# design.net
KiCad netlist of a schematic drawn in Altium Designer
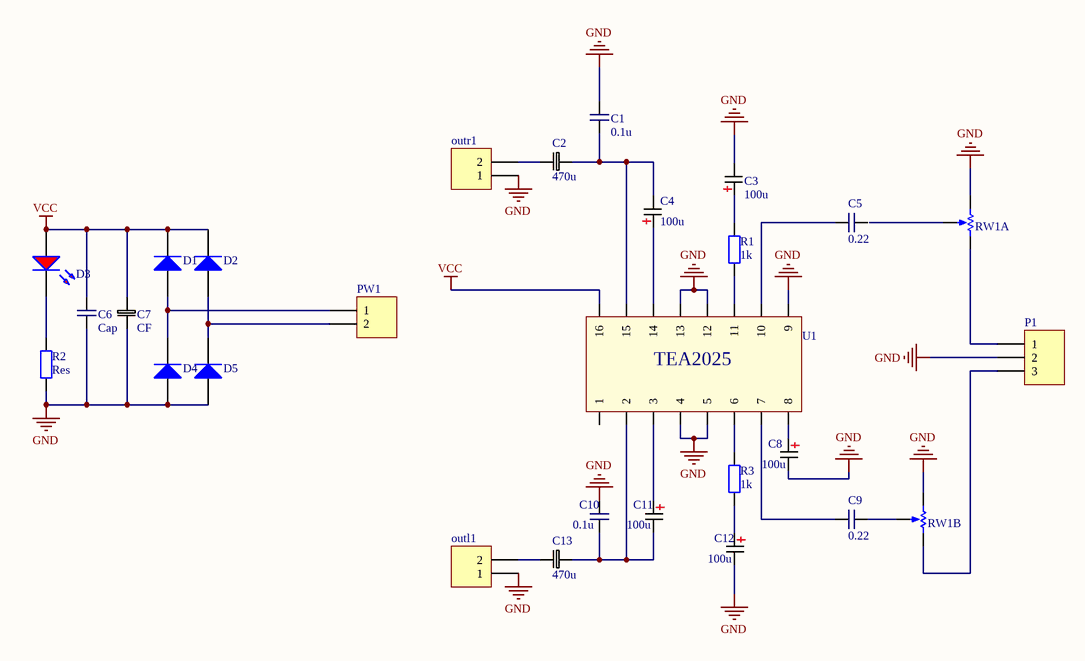
[diagram p0: 原理图.SchDoc]

(export (version "E")
  (design (tool "Eeschema 10.0.6"))
  (components
    (comp (ref "C1") (value "0.1u") (footprint "RAD0.1") (libsource (lib "Schlib1") (part "Cap")))
    (comp (ref "C2") (value "470u") (footprint "CF0.1-6.5") (libsource (lib "Schlib1") (part "CF")))
    (comp (ref "C3") (value "100u") (footprint "CF0.1") (libsource (lib "Schlib1") (part "Cap Pol")))
    (comp (ref "C4") (value "100u") (footprint "CF0.1") (libsource (lib "Schlib1") (part "Cap Pol")))
    (comp (ref "C5") (value "0.22") (footprint "RAD0.1") (libsource (lib "Schlib1") (part "Cap")))
    (comp (ref "C6") (value "Cap") (footprint "RAD0.1") (libsource (lib "MY") (part "Cap")))
    (comp (ref "C7") (value "CF") (footprint "CF0.2-13") (libsource (lib "MY") (part "CF")))
    (comp (ref "C8") (value "100u") (footprint "CF0.2-13") (libsource (lib "Schlib1") (part "Cap Pol")))
    (comp (ref "C9") (value "0.22") (footprint "RAD0.1") (libsource (lib "Schlib1") (part "Cap")))
    (comp (ref "C10") (value "0.1u") (footprint "RAD0.1") (libsource (lib "Schlib1") (part "Cap")))
    (comp (ref "C11") (value "100u") (footprint "CF0.1") (libsource (lib "Schlib1") (part "Cap Pol")))
    (comp (ref "C12") (value "100u") (footprint "CF0.1") (libsource (lib "Schlib1") (part "Cap Pol")))
    (comp (ref "C13") (value "470u") (footprint "CF0.1-6.5") (libsource (lib "Schlib1") (part "CF")))
    (comp (ref "D1")
      (value "Diode 1N4007")
      (footprint "DIO10.46-5.3x2.8")
      (description "1 Amp General Purpose Rectifier")
      (fields (field (name "PUBLISHER") "Altium Limited"))
      (libsource (lib "Miscellaneous Devices") (part "Diode 1N4007"))
    )
    (comp (ref "D2")
      (value "Diode 1N4007")
      (footprint "DIO10.46-5.3x2.8")
      (description "1 Amp General Purpose Rectifier")
      (fields (field (name "PUBLISHER") "Altium Limited"))
      (libsource (lib "Miscellaneous Devices") (part "Diode 1N4007"))
    )
    (comp (ref "D3")
      (value "LED0")
      (footprint "LED")
      (fields (field (name "PUBLISHER") "Altium Limited"))
      (libsource (lib "MY") (part "LED0"))
    )
    (comp (ref "D4")
      (value "Diode 1N4007")
      (footprint "DIO10.46-5.3x2.8")
      (description "1 Amp General Purpose Rectifier")
      (fields (field (name "PUBLISHER") "Altium Limited"))
      (libsource (lib "Miscellaneous Devices") (part "Diode 1N4007"))
    )
    (comp (ref "D5")
      (value "Diode 1N4007")
      (footprint "DIO10.46-5.3x2.8")
      (description "1 Amp General Purpose Rectifier")
      (fields (field (name "PUBLISHER") "Altium Limited"))
      (libsource (lib "Miscellaneous Devices") (part "Diode 1N4007"))
    )
    (comp (ref "outl1")
      (value "Header 2")
      (footprint "HDR1X2")
      (description "Header, 2-Pin")
      (fields (field (name "PUBLISHER") "Altium Limited"))
      (libsource (lib "") (part "Header 2_1"))
    )
    (comp (ref "outr1")
      (value "Header 2")
      (footprint "HDR1X2")
      (description "Header, 2-Pin")
      (fields (field (name "PUBLISHER") "Altium Limited"))
      (libsource (lib "") (part "Header 2_1"))
    )
    (comp (ref "P1")
      (value "Header 3")
      (footprint "HDR1X3")
      (description "Header, 3-Pin")
      (fields (field (name "PUBLISHER") "Altium Limited"))
      (libsource (lib "Miscellaneous Connectors") (part "Header 3"))
    )
    (comp (ref "PW1")
      (value "Header 2")
      (footprint "HDR1X2")
      (description "Header, 2-Pin")
      (fields (field (name "PUBLISHER") "Altium Limited"))
      (libsource (lib "Miscellaneous Connectors") (part "Header 2"))
    )
    (comp (ref "R1")
      (value "1k")
      (footprint "RAD0.1")
      (description "Resistor")
      (fields (field (name "PUBLISHER") "Altium Limited"))
      (libsource (lib "") (part "Res_1"))
    )
    (comp (ref "R2")
      (value "Res")
      (footprint "AXIAL-0.3")
      (description "Resistor")
      (fields (field (name "PUBLISHER") "Altium Limited"))
      (libsource (lib "MY") (part "Res"))
    )
    (comp (ref "R3")
      (value "1k")
      (footprint "RAD0.1")
      (description "Resistor")
      (fields (field (name "PUBLISHER") "Altium Limited"))
      (libsource (lib "Schlib1") (part "Res"))
    )
    (comp (ref "RW1") (value "RW") (footprint "RW") (libsource (lib "Schlib1") (part "RW")))
    (comp (ref "U1") (value "TEA2025") (footprint "DIP16") (libsource (lib "Schlib1") (part "TEA2025")))
  )
  (nets
    (net (code "1") (name "GND") (class "Default")
      (node (ref "C1") (pin "1") (pinfunction "1_1") (pintype "passive"))
      (node (ref "C10") (pin "1") (pinfunction "1_1") (pintype "passive"))
      (node (ref "C12") (pin "2") (pinfunction "2_2") (pintype "passive"))
      (node (ref "C3") (pin "2") (pinfunction "2_2") (pintype "passive"))
      (node (ref "C6") (pin "1") (pinfunction "1_1") (pintype "passive"))
      (node (ref "C7") (pin "2") (pinfunction "2_2") (pintype "passive"))
      (node (ref "C8") (pin "2") (pinfunction "2_2") (pintype "passive"))
      (node (ref "D4") (pin "1") (pinfunction "A_1") (pintype "passive"))
      (node (ref "D5") (pin "1") (pinfunction "A_1") (pintype "passive"))
      (node (ref "P1") (pin "2") (pinfunction "2_2") (pintype "passive"))
      (node (ref "R2") (pin "1") (pinfunction "1_1") (pintype "passive"))
      (node (ref "RW1") (pin "1") (pinfunction "TOP_1") (pintype "passive"))
      (node (ref "RW1") (pin "4") (pinfunction "TOP_4") (pintype "passive"))
      (node (ref "U1") (pin "12") (pinfunction "12_12") (pintype "passive"))
      (node (ref "U1") (pin "13") (pinfunction "13_13") (pintype "passive"))
      (node (ref "U1") (pin "4") (pinfunction "4_4") (pintype "passive"))
      (node (ref "U1") (pin "5") (pinfunction "5_5") (pintype "passive"))
      (node (ref "U1") (pin "9") (pinfunction "9_9") (pintype "passive"))
      (node (ref "outl1") (pin "1") (pinfunction "1_1") (pintype "passive"))
      (node (ref "outr1") (pin "1") (pinfunction "1_1") (pintype "passive"))
    )
    (net (code "2") (name "Net-(C1-Pad2)") (class "Default")
      (node (ref "C1") (pin "2") (pinfunction "2_2") (pintype "passive"))
      (node (ref "C2") (pin "1") (pinfunction "1_1") (pintype "passive"))
      (node (ref "C4") (pin "2") (pinfunction "2_2") (pintype "passive"))
      (node (ref "U1") (pin "15") (pinfunction "15_15") (pintype "passive"))
    )
    (net (code "3") (name "Net-(C2-Pad2)") (class "Default")
      (node (ref "C2") (pin "2") (pinfunction "2_2") (pintype "passive"))
      (node (ref "outr1") (pin "2") (pinfunction "2_2") (pintype "passive"))
    )
    (net (code "4") (name "Net-(C3-Pad1)") (class "Default")
      (node (ref "C3") (pin "1") (pinfunction "1_1") (pintype "passive"))
      (node (ref "R1") (pin "1") (pinfunction "1_1") (pintype "passive"))
    )
    (net (code "5") (name "Net-(C4-Pad1)") (class "Default")
      (node (ref "C4") (pin "1") (pinfunction "1_1") (pintype "passive"))
      (node (ref "U1") (pin "14") (pinfunction "14_14") (pintype "passive"))
    )
    (net (code "6") (name "Net-(C5-Pad1)") (class "Default")
      (node (ref "C5") (pin "1") (pinfunction "1_1") (pintype "passive"))
      (node (ref "U1") (pin "10") (pinfunction "10_10") (pintype "passive"))
    )
    (net (code "7") (name "Net-(C8-Pad1)") (class "Default")
      (node (ref "C8") (pin "1") (pinfunction "1_1") (pintype "passive"))
      (node (ref "U1") (pin "8") (pinfunction "8_8") (pintype "passive"))
    )
    (net (code "8") (name "Net-(C9-Pad1)") (class "Default")
      (node (ref "C9") (pin "1") (pinfunction "1_1") (pintype "passive"))
      (node (ref "U1") (pin "7") (pinfunction "7_7") (pintype "passive"))
    )
    (net (code "9") (name "Net-(C10-Pad2)") (class "Default")
      (node (ref "C10") (pin "2") (pinfunction "2_2") (pintype "passive"))
      (node (ref "C11") (pin "2") (pinfunction "2_2") (pintype "passive"))
      (node (ref "C13") (pin "1") (pinfunction "1_1") (pintype "passive"))
      (node (ref "U1") (pin "2") (pinfunction "2_2") (pintype "passive"))
    )
    (net (code "10") (name "Net-(C11-Pad1)") (class "Default")
      (node (ref "C11") (pin "1") (pinfunction "1_1") (pintype "passive"))
      (node (ref "U1") (pin "3") (pinfunction "3_3") (pintype "passive"))
    )
    (net (code "11") (name "Net-(C12-Pad1)") (class "Default")
      (node (ref "C12") (pin "1") (pinfunction "1_1") (pintype "passive"))
      (node (ref "R3") (pin "1") (pinfunction "1_1") (pintype "passive"))
    )
    (net (code "12") (name "Net-(C13-Pad2)") (class "Default")
      (node (ref "C13") (pin "2") (pinfunction "2_2") (pintype "passive"))
      (node (ref "outl1") (pin "2") (pinfunction "2_2") (pintype "passive"))
    )
    (net (code "13") (name "Net-(D1-A)") (class "Default")
      (node (ref "D1") (pin "1") (pinfunction "A_1") (pintype "passive"))
      (node (ref "D4") (pin "2") (pinfunction "K_2") (pintype "passive"))
      (node (ref "PW1") (pin "1") (pinfunction "1_1") (pintype "passive"))
    )
    (net (code "14") (name "Net-(D2-A)") (class "Default")
      (node (ref "D2") (pin "1") (pinfunction "A_1") (pintype "passive"))
      (node (ref "D5") (pin "2") (pinfunction "K_2") (pintype "passive"))
      (node (ref "PW1") (pin "2") (pinfunction "2_2") (pintype "passive"))
    )
    (net (code "15") (name "Net-(D3-K)") (class "Default")
      (node (ref "D3") (pin "2") (pinfunction "K_2") (pintype "passive"))
      (node (ref "R2") (pin "2") (pinfunction "2_2") (pintype "passive"))
    )
    (net (code "16") (name "Net-(R1-Pad2)") (class "Default")
      (node (ref "R1") (pin "2") (pinfunction "2_2") (pintype "passive"))
      (node (ref "U1") (pin "11") (pinfunction "11_11") (pintype "passive"))
    )
    (net (code "17") (name "Net-(R3-Pad2)") (class "Default")
      (node (ref "R3") (pin "2") (pinfunction "2_2") (pintype "passive"))
      (node (ref "U1") (pin "6") (pinfunction "6_6") (pintype "passive"))
    )
    (net (code "18") (name "Net-(RW1A-BOT)") (class "Default")
      (node (ref "P1") (pin "1") (pinfunction "1_1") (pintype "passive"))
      (node (ref "RW1") (pin "3") (pinfunction "BOT_3") (pintype "passive"))
    )
    (net (code "19") (name "Net-(RW1B-BOT)") (class "Default")
      (node (ref "P1") (pin "3") (pinfunction "3_3") (pintype "passive"))
      (node (ref "RW1") (pin "6") (pinfunction "BOT_6") (pintype "passive"))
    )
    (net (code "20") (name "Net-(RW1B-TAP)") (class "Default")
      (node (ref "C9") (pin "2") (pinfunction "2_2") (pintype "passive"))
      (node (ref "RW1") (pin "5") (pinfunction "TAP_5") (pintype "passive"))
    )
    (net (code "21") (name "VCC") (class "Default")
      (node (ref "C6") (pin "2") (pinfunction "2_2") (pintype "passive"))
      (node (ref "C7") (pin "1") (pinfunction "1_1") (pintype "passive"))
      (node (ref "D1") (pin "2") (pinfunction "K_2") (pintype "passive"))
      (node (ref "D2") (pin "2") (pinfunction "K_2") (pintype "passive"))
      (node (ref "D3") (pin "1") (pinfunction "A_1") (pintype "passive"))
      (node (ref "U1") (pin "16") (pinfunction "16_16") (pintype "passive"))
    )
    (net (code "22") (name "unconnected-(C5-Pad2)") (class "Default")
      (node (ref "C5") (pin "2") (pinfunction "2_2") (pintype "passive"))
    )
    (net (code "23") (name "unconnected-(RW1A-TAP-Pad2)") (class "Default")
      (node (ref "RW1") (pin "2") (pinfunction "TAP_2") (pintype "passive"))
    )
    (net (code "24") (name "unconnected-(U1-Pad1)") (class "Default")
      (node (ref "U1") (pin "1") (pinfunction "1_1") (pintype "passive"))
    )
  )
)
